# CAN.net
KiCad netlist of a schematic drawn in EAGLE
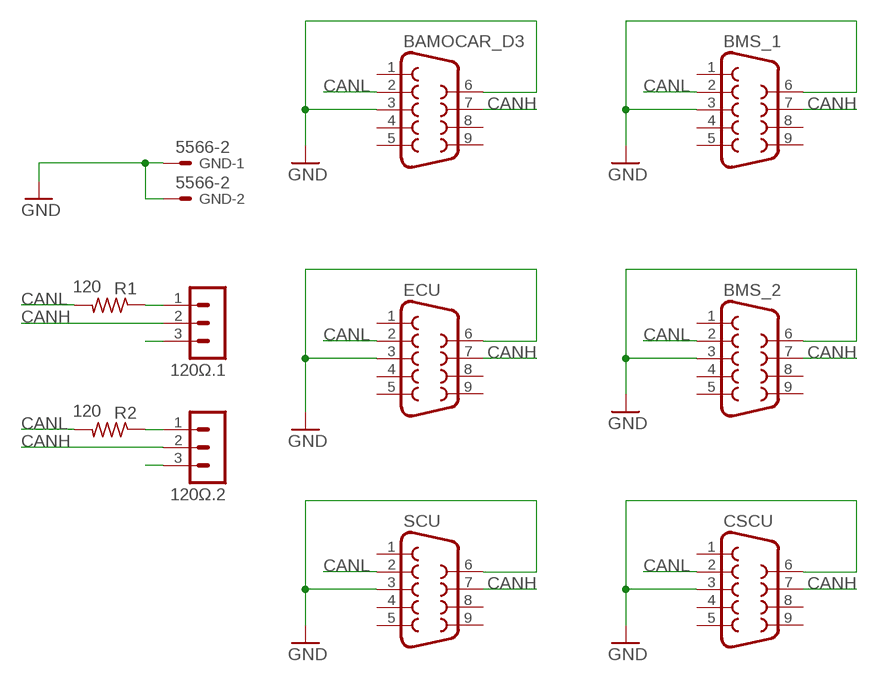
[diagram p0: schematic, sheet 1]

(export (version "E")
  (design (tool "Eeschema 10.0.6"))
  (components
    (comp (ref "120Ω.1")
      (value "MA03-1")
      (footprint "eagle-import:MA03-1")
      (libsource (lib "eagle-import") (part "MA03-1"))
    )
    (comp (ref "120Ω.2")
      (value "MA03-1")
      (footprint "eagle-import:MA03-1")
      (libsource (lib "eagle-import") (part "MA03-1"))
    )
    (comp (ref "BAMOCAR_D3")
      (value "F09VP")
      (footprint "eagle-import:F09VP")
      (libsource (lib "eagle-import") (part "F09VP"))
    )
    (comp (ref "BMS_1")
      (value "F09VP")
      (footprint "eagle-import:F09VP")
      (libsource (lib "eagle-import") (part "F09VP"))
    )
    (comp (ref "BMS_2")
      (value "F09VP")
      (footprint "eagle-import:F09VP")
      (libsource (lib "eagle-import") (part "F09VP"))
    )
    (comp (ref "CSCU")
      (value "F09VP")
      (footprint "eagle-import:F09VP")
      (libsource (lib "eagle-import") (part "F09VP"))
    )
    (comp (ref "ECU")
      (value "F09VP")
      (footprint "eagle-import:F09VP")
      (libsource (lib "eagle-import") (part "F09VP"))
    )
    (comp (ref "GND")
      (value "5566-2")
      (footprint "eagle-import:5566-2")
      (fields (field (name "MF") "MOLEX"))
      (libsource (lib "eagle-import") (part "5566-2"))
    )
    (comp (ref "R1")
      (value "120")
      (footprint "eagle-import:R0805")
      (libsource (lib "eagle-import") (part "R-US_R0805"))
    )
    (comp (ref "R2")
      (value "120")
      (footprint "eagle-import:R0805")
      (libsource (lib "eagle-import") (part "R-US_R0805"))
    )
    (comp (ref "SCU")
      (value "F09VP")
      (footprint "eagle-import:F09VP")
      (libsource (lib "eagle-import") (part "F09VP"))
    )
  )
  (nets
    (net (code "1") (name "/CANH") (class "Default")
      (node (ref "120Ω.1") (pin "2") (pinfunction "2_2") (pintype "passive"))
      (node (ref "120Ω.2") (pin "2") (pinfunction "2_2") (pintype "passive"))
      (node (ref "BAMOCAR_D3") (pin "7") (pinfunction "7_7") (pintype "passive"))
      (node (ref "BMS_1") (pin "7") (pinfunction "7_7") (pintype "passive"))
      (node (ref "BMS_2") (pin "7") (pinfunction "7_7") (pintype "passive"))
      (node (ref "CSCU") (pin "7") (pinfunction "7_7") (pintype "passive"))
      (node (ref "ECU") (pin "7") (pinfunction "7_7") (pintype "passive"))
      (node (ref "SCU") (pin "7") (pinfunction "7_7") (pintype "passive"))
    )
    (net (code "2") (name "/CANL") (class "Default")
      (node (ref "BAMOCAR_D3") (pin "2") (pinfunction "2_2") (pintype "passive"))
      (node (ref "BMS_1") (pin "2") (pinfunction "2_2") (pintype "passive"))
      (node (ref "BMS_2") (pin "2") (pinfunction "2_2") (pintype "passive"))
      (node (ref "CSCU") (pin "2") (pinfunction "2_2") (pintype "passive"))
      (node (ref "ECU") (pin "2") (pinfunction "2_2") (pintype "passive"))
      (node (ref "R1") (pin "2") (pinfunction "2_2") (pintype "passive"))
      (node (ref "R2") (pin "2") (pinfunction "2_2") (pintype "passive"))
      (node (ref "SCU") (pin "2") (pinfunction "2_2") (pintype "passive"))
    )
    (net (code "3") (name "GND") (class "Default")
      (node (ref "BAMOCAR_D3") (pin "3") (pinfunction "3_3") (pintype "passive"))
      (node (ref "BAMOCAR_D3") (pin "6") (pinfunction "6_6") (pintype "passive"))
      (node (ref "BMS_1") (pin "3") (pinfunction "3_3") (pintype "passive"))
      (node (ref "BMS_1") (pin "6") (pinfunction "6_6") (pintype "passive"))
      (node (ref "BMS_2") (pin "3") (pinfunction "3_3") (pintype "passive"))
      (node (ref "BMS_2") (pin "6") (pinfunction "6_6") (pintype "passive"))
      (node (ref "CSCU") (pin "3") (pinfunction "3_3") (pintype "passive"))
      (node (ref "CSCU") (pin "6") (pinfunction "6_6") (pintype "passive"))
      (node (ref "ECU") (pin "3") (pinfunction "3_3") (pintype "passive"))
      (node (ref "ECU") (pin "6") (pinfunction "6_6") (pintype "passive"))
      (node (ref "GND") (pin "1") (pinfunction "S_1") (pintype "passive"))
      (node (ref "GND") (pin "2") (pinfunction "S_2") (pintype "passive"))
      (node (ref "SCU") (pin "3") (pinfunction "3_3") (pintype "passive"))
      (node (ref "SCU") (pin "6") (pinfunction "6_6") (pintype "passive"))
    )
    (net (code "4") (name "Net-(120Ω.1-Pad1)") (class "Default")
      (node (ref "120Ω.1") (pin "1") (pinfunction "1_1") (pintype "passive"))
      (node (ref "R1") (pin "1") (pinfunction "1_1") (pintype "passive"))
    )
    (net (code "5") (name "Net-(120Ω.2-Pad1)") (class "Default")
      (node (ref "120Ω.2") (pin "1") (pinfunction "1_1") (pintype "passive"))
      (node (ref "R2") (pin "1") (pinfunction "1_1") (pintype "passive"))
    )
    (net (code "6") (name "unconnected-(120Ω.1-Pad3)") (class "Default")
      (node (ref "120Ω.1") (pin "3") (pinfunction "3_3") (pintype "passive"))
    )
    (net (code "7") (name "unconnected-(120Ω.2-Pad3)") (class "Default")
      (node (ref "120Ω.2") (pin "3") (pinfunction "3_3") (pintype "passive"))
    )
    (net (code "8") (name "unconnected-(BAMOCAR_D3-Pad1)") (class "Default")
      (node (ref "BAMOCAR_D3") (pin "1") (pinfunction "1_1") (pintype "passive"))
    )
    (net (code "9") (name "unconnected-(BAMOCAR_D3-Pad4)") (class "Default")
      (node (ref "BAMOCAR_D3") (pin "4") (pinfunction "4_4") (pintype "passive"))
    )
    (net (code "10") (name "unconnected-(BAMOCAR_D3-Pad5)") (class "Default")
      (node (ref "BAMOCAR_D3") (pin "5") (pinfunction "5_5") (pintype "passive"))
    )
    (net (code "11") (name "unconnected-(BAMOCAR_D3-Pad8)") (class "Default")
      (node (ref "BAMOCAR_D3") (pin "8") (pinfunction "8_8") (pintype "passive"))
    )
    (net (code "12") (name "unconnected-(BAMOCAR_D3-Pad9)") (class "Default")
      (node (ref "BAMOCAR_D3") (pin "9") (pinfunction "9_9") (pintype "passive"))
    )
    (net (code "13") (name "unconnected-(BMS_1-Pad1)") (class "Default")
      (node (ref "BMS_1") (pin "1") (pinfunction "1_1") (pintype "passive"))
    )
    (net (code "14") (name "unconnected-(BMS_1-Pad4)") (class "Default")
      (node (ref "BMS_1") (pin "4") (pinfunction "4_4") (pintype "passive"))
    )
    (net (code "15") (name "unconnected-(BMS_1-Pad5)") (class "Default")
      (node (ref "BMS_1") (pin "5") (pinfunction "5_5") (pintype "passive"))
    )
    (net (code "16") (name "unconnected-(BMS_1-Pad8)") (class "Default")
      (node (ref "BMS_1") (pin "8") (pinfunction "8_8") (pintype "passive"))
    )
    (net (code "17") (name "unconnected-(BMS_1-Pad9)") (class "Default")
      (node (ref "BMS_1") (pin "9") (pinfunction "9_9") (pintype "passive"))
    )
    (net (code "18") (name "unconnected-(BMS_2-Pad1)") (class "Default")
      (node (ref "BMS_2") (pin "1") (pinfunction "1_1") (pintype "passive"))
    )
    (net (code "19") (name "unconnected-(BMS_2-Pad4)") (class "Default")
      (node (ref "BMS_2") (pin "4") (pinfunction "4_4") (pintype "passive"))
    )
    (net (code "20") (name "unconnected-(BMS_2-Pad5)") (class "Default")
      (node (ref "BMS_2") (pin "5") (pinfunction "5_5") (pintype "passive"))
    )
    (net (code "21") (name "unconnected-(BMS_2-Pad8)") (class "Default")
      (node (ref "BMS_2") (pin "8") (pinfunction "8_8") (pintype "passive"))
    )
    (net (code "22") (name "unconnected-(BMS_2-Pad9)") (class "Default")
      (node (ref "BMS_2") (pin "9") (pinfunction "9_9") (pintype "passive"))
    )
    (net (code "23") (name "unconnected-(CSCU-Pad1)") (class "Default")
      (node (ref "CSCU") (pin "1") (pinfunction "1_1") (pintype "passive"))
    )
    (net (code "24") (name "unconnected-(CSCU-Pad4)") (class "Default")
      (node (ref "CSCU") (pin "4") (pinfunction "4_4") (pintype "passive"))
    )
    (net (code "25") (name "unconnected-(CSCU-Pad5)") (class "Default")
      (node (ref "CSCU") (pin "5") (pinfunction "5_5") (pintype "passive"))
    )
    (net (code "26") (name "unconnected-(CSCU-Pad8)") (class "Default")
      (node (ref "CSCU") (pin "8") (pinfunction "8_8") (pintype "passive"))
    )
    (net (code "27") (name "unconnected-(CSCU-Pad9)") (class "Default")
      (node (ref "CSCU") (pin "9") (pinfunction "9_9") (pintype "passive"))
    )
    (net (code "28") (name "unconnected-(ECU-Pad1)") (class "Default")
      (node (ref "ECU") (pin "1") (pinfunction "1_1") (pintype "passive"))
    )
    (net (code "29") (name "unconnected-(ECU-Pad4)") (class "Default")
      (node (ref "ECU") (pin "4") (pinfunction "4_4") (pintype "passive"))
    )
    (net (code "30") (name "unconnected-(ECU-Pad5)") (class "Default")
      (node (ref "ECU") (pin "5") (pinfunction "5_5") (pintype "passive"))
    )
    (net (code "31") (name "unconnected-(ECU-Pad8)") (class "Default")
      (node (ref "ECU") (pin "8") (pinfunction "8_8") (pintype "passive"))
    )
    (net (code "32") (name "unconnected-(ECU-Pad9)") (class "Default")
      (node (ref "ECU") (pin "9") (pinfunction "9_9") (pintype "passive"))
    )
    (net (code "33") (name "unconnected-(SCU-Pad1)") (class "Default")
      (node (ref "SCU") (pin "1") (pinfunction "1_1") (pintype "passive"))
    )
    (net (code "34") (name "unconnected-(SCU-Pad4)") (class "Default")
      (node (ref "SCU") (pin "4") (pinfunction "4_4") (pintype "passive"))
    )
    (net (code "35") (name "unconnected-(SCU-Pad5)") (class "Default")
      (node (ref "SCU") (pin "5") (pinfunction "5_5") (pintype "passive"))
    )
    (net (code "36") (name "unconnected-(SCU-Pad8)") (class "Default")
      (node (ref "SCU") (pin "8") (pinfunction "8_8") (pintype "passive"))
    )
    (net (code "37") (name "unconnected-(SCU-Pad9)") (class "Default")
      (node (ref "SCU") (pin "9") (pinfunction "9_9") (pintype "passive"))
    )
  )
)
